# LH200K-IF05_240x320_TFT_LCD_Module.net
KiCad netlist of a schematic drawn in Altium Designer
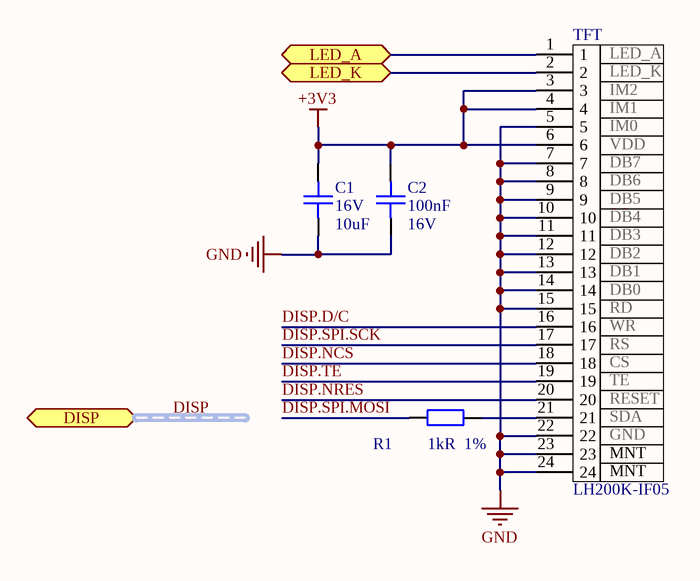
[diagram p0: LH200K-IF05_240x320_TFT_LCD_Module.SchDoc]

(export (version "E")
  (design (tool "Eeschema 10.0.6"))
  (components
    (comp (ref "C1")
      (value "CAP CER 10UF 16V X5R 0603")
      (footprint "C0603")
      (description "10µF ±10% 16V Ceramic Capacitor X5R 0603 (1608 Metric)")
      (fields
        (field (name "MANUFACTURER") "Murata")
        (field (name "MANUFACTURER PART NUMBER") "GRM188R61C106KAALJ")
        (field (name "VOLTAGE RATING") "16V")
        (field (name "CAPACITANCE") "10uF")
      )
      (libsource (lib "capacitors_smd") (part "CAP CER 10UF 16V X5R 0603"))
    )
    (comp (ref "C2")
      (value "CAP CER 0.1UF 16V X7R 0402")
      (footprint "C0402")
      (description "0.1µF ±10% 16V Ceramic Capacitor X7R 0402 (1005 Metric)")
      (fields
        (field (name "MANUFACTURER PART NUMBER") "CC0402KRX7R7BB104")
        (field (name "MANUFACTURER") "Yageo")
        (field (name "CAPACITANCE") "100nF")
        (field (name "VOLTAGE") "16V")
      )
      (libsource (lib "capacitors_smd") (part "CAP CER 0.1UF 16V X7R 0402"))
    )
    (comp (ref "R1")
      (value "RES SMD 1K OHM 1% 1/16W 0402")
      (footprint "R0402")
      (description "1 kOhms ±1% 0.063W, 1/16W Chip Resistor 0402 (1005 Metric) Moisture Resistant Thick Film")
      (fields
        (field (name "MANUFACTURER") "Yageo")
        (field (name "MANUFACTURER PART NUMBER") "RC0402FR-071KL")
        (field (name "TOLERANCE") "1%")
        (field (name "RESISTANCE") "1kR")
      )
      (libsource (lib "resistors_smd") (part "RES SMD 1K OHM 1% 1/16W 0402"))
    )
    (comp (ref "TFT")
      (value "LH200K-IF05")
      (footprint "CONN_0524352271")
      (description "22 Position FFC, FPC Connector Contacts, Top 0.020\" (0.50mm) Surface Mount, Right Angle")
      (fields
        (field (name "MANUFACTURER") "Molex")
        (field (name "MANUFACTURER PART NUMBER") "0524352271")
        (field (name "PIN_1") "LED_A")
        (field (name "PIN_2") "LED_K")
        (field (name "PIN_3") "IM2")
        (field (name "PIN_4") "IM1")
        (field (name "PIN_5") "IM0")
        (field (name "PIN_6") "VDD")
        (field (name "PIN_7") "DB7")
        (field (name "PIN_8") "DB6")
        (field (name "PIN_9") "DB5")
        (field (name "PIN_10") "DB4")
        (field (name "PIN_11") "DB3")
        (field (name "PIN_12") "DB2")
        (field (name "PIN_13") "DB1")
        (field (name "PIN_14") "DB0")
        (field (name "PIN_15") "RD")
        (field (name "PIN_16") "WR")
        (field (name "PIN_17") "RS")
        (field (name "PIN_18") "CS")
        (field (name "PIN_19") "TE")
        (field (name "PIN_20") "RESET")
        (field (name "PIN_21") "SDA")
        (field (name "PIN_22") "GND")
        (field (name "PIN_23") "MNT")
        (field (name "PIN_24") "MNT")
      )
      (libsource (lib "BLDC_Motor_Driver") (part "CONN 0524352271 FFC TOP 22POS 0.50MM R/A"))
    )
  )
  (nets
    (net (code "2") (name "+3V3") (class "Default")
      (node (ref "C1") (pin "1") (pinfunction "1_1") (pintype "passive"))
      (node (ref "C2") (pin "1") (pinfunction "1_1") (pintype "passive"))
      (node (ref "TFT") (pin "3") (pinfunction "3_3") (pintype "passive"))
      (node (ref "TFT") (pin "4") (pinfunction "4_4") (pintype "passive"))
      (node (ref "TFT") (pin "6") (pinfunction "6_6") (pintype "passive"))
    )
    (net (code "3") (name "/DISP.D{slash}C") (class "Default")
      (node (ref "TFT") (pin "16") (pinfunction "16_16") (pintype "passive"))
    )
    (net (code "4") (name "/DISP.NCS") (class "Default")
      (node (ref "TFT") (pin "18") (pinfunction "18_18") (pintype "passive"))
    )
    (net (code "5") (name "/DISP.NRES") (class "Default")
      (node (ref "TFT") (pin "20") (pinfunction "20_20") (pintype "passive"))
    )
    (net (code "6") (name "/DISP.SPI.MOSI") (class "Default")
      (node (ref "R1") (pin "1") (pinfunction "1_1") (pintype "passive"))
    )
    (net (code "7") (name "/DISP.SPI.SCK") (class "Default")
      (node (ref "TFT") (pin "17") (pinfunction "17_17") (pintype "passive"))
    )
    (net (code "8") (name "/DISP.TE") (class "Default")
      (node (ref "TFT") (pin "19") (pinfunction "19_19") (pintype "passive"))
    )
    (net (code "9") (name "/LED_A") (class "Default")
      (node (ref "TFT") (pin "1") (pinfunction "1_1") (pintype "passive"))
    )
    (net (code "10") (name "/LED_K") (class "Default")
      (node (ref "TFT") (pin "2") (pinfunction "2_2") (pintype "passive"))
    )
    (net (code "12") (name "GND") (class "Default")
      (node (ref "C1") (pin "2") (pinfunction "2_2") (pintype "passive"))
      (node (ref "C2") (pin "2") (pinfunction "2_2") (pintype "passive"))
      (node (ref "TFT") (pin "10") (pinfunction "10_10") (pintype "passive"))
      (node (ref "TFT") (pin "11") (pinfunction "11_11") (pintype "passive"))
      (node (ref "TFT") (pin "12") (pinfunction "12_12") (pintype "passive"))
      (node (ref "TFT") (pin "13") (pinfunction "13_13") (pintype "passive"))
      (node (ref "TFT") (pin "14") (pinfunction "14_14") (pintype "passive"))
      (node (ref "TFT") (pin "15") (pinfunction "15_15") (pintype "passive"))
      (node (ref "TFT") (pin "22") (pinfunction "22_22") (pintype "passive"))
      (node (ref "TFT") (pin "23") (pinfunction "23_23") (pintype "passive"))
      (node (ref "TFT") (pin "24") (pinfunction "24_24") (pintype "passive"))
      (node (ref "TFT") (pin "5") (pinfunction "5_5") (pintype "passive"))
      (node (ref "TFT") (pin "7") (pinfunction "7_7") (pintype "passive"))
      (node (ref "TFT") (pin "8") (pinfunction "8_8") (pintype "passive"))
      (node (ref "TFT") (pin "9") (pinfunction "9_9") (pintype "passive"))
    )
    (net (code "13") (name "Net-(R1-Pad2)") (class "Default")
      (node (ref "R1") (pin "2") (pinfunction "2_2") (pintype "passive"))
      (node (ref "TFT") (pin "21") (pinfunction "21_21") (pintype "passive"))
    )
  )
)
